# 03_cellular.net
KiCad netlist of a schematic drawn in Altium Designer
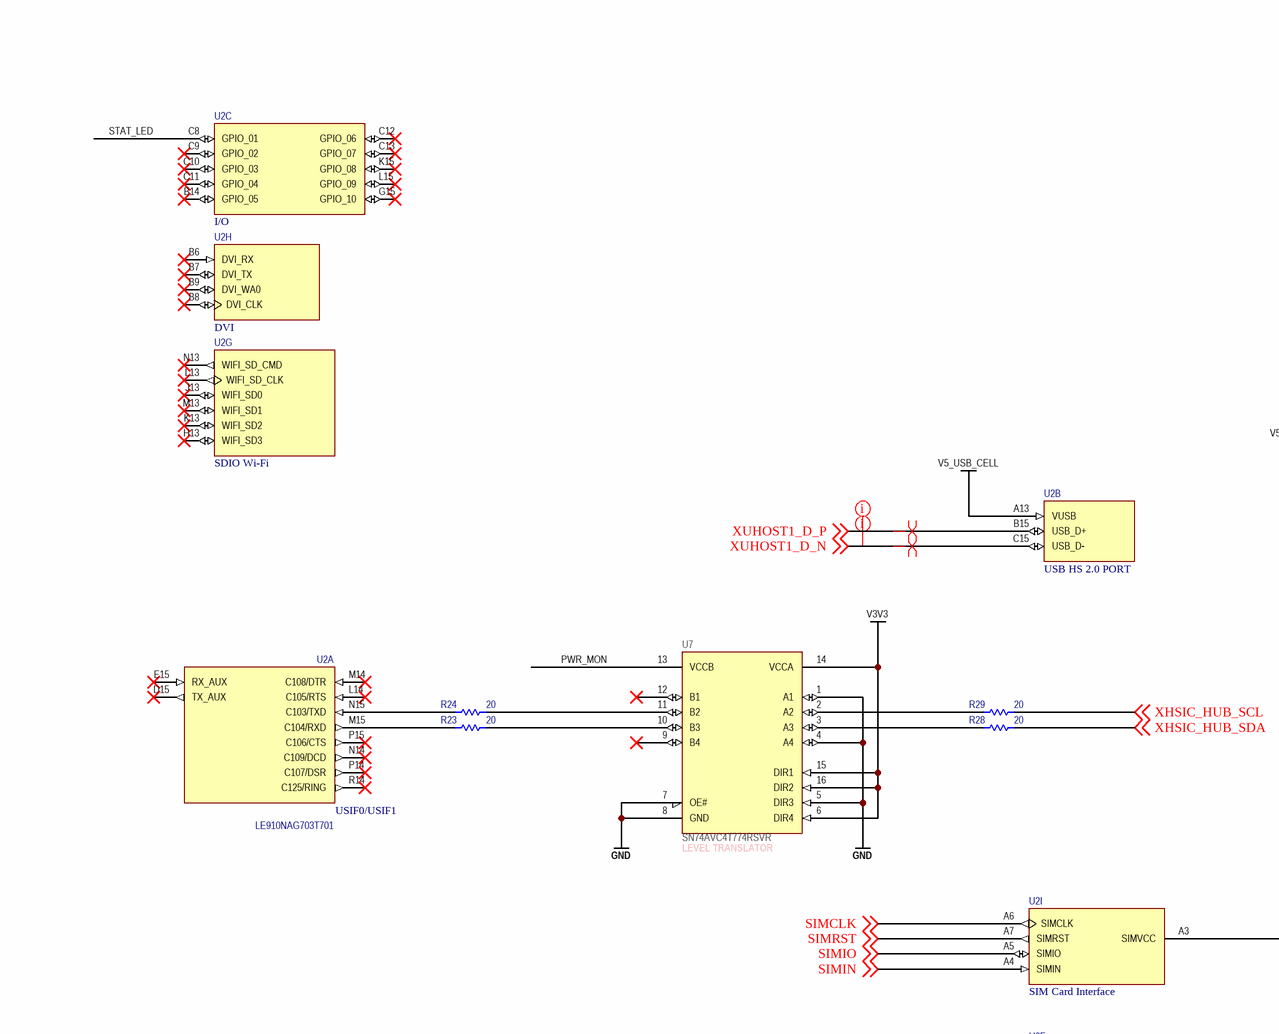
[diagram p0: 03_cellular.SchDoc, top left]
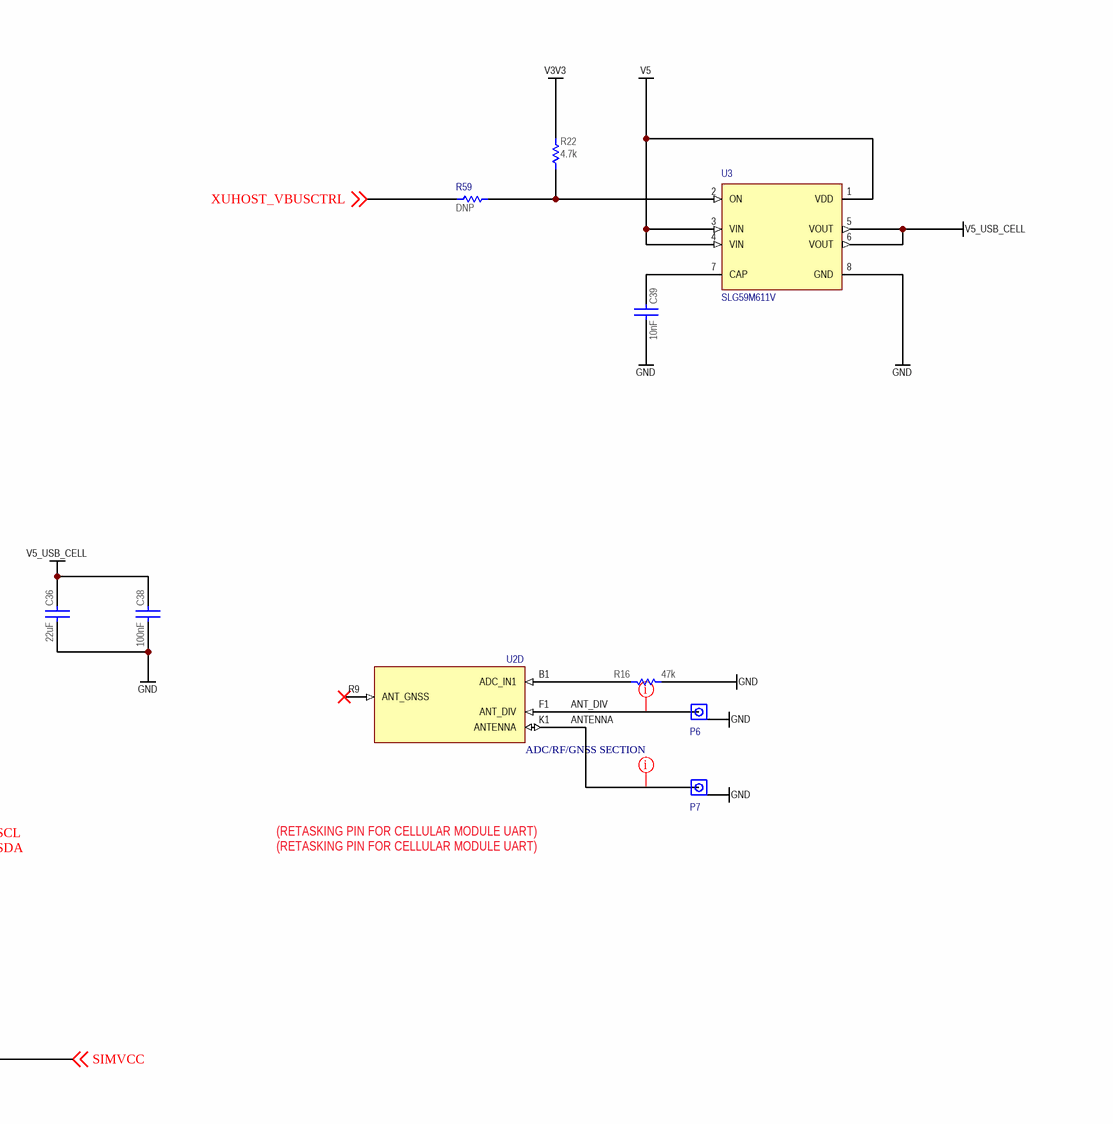
[diagram p1: 03_cellular.SchDoc, top right]
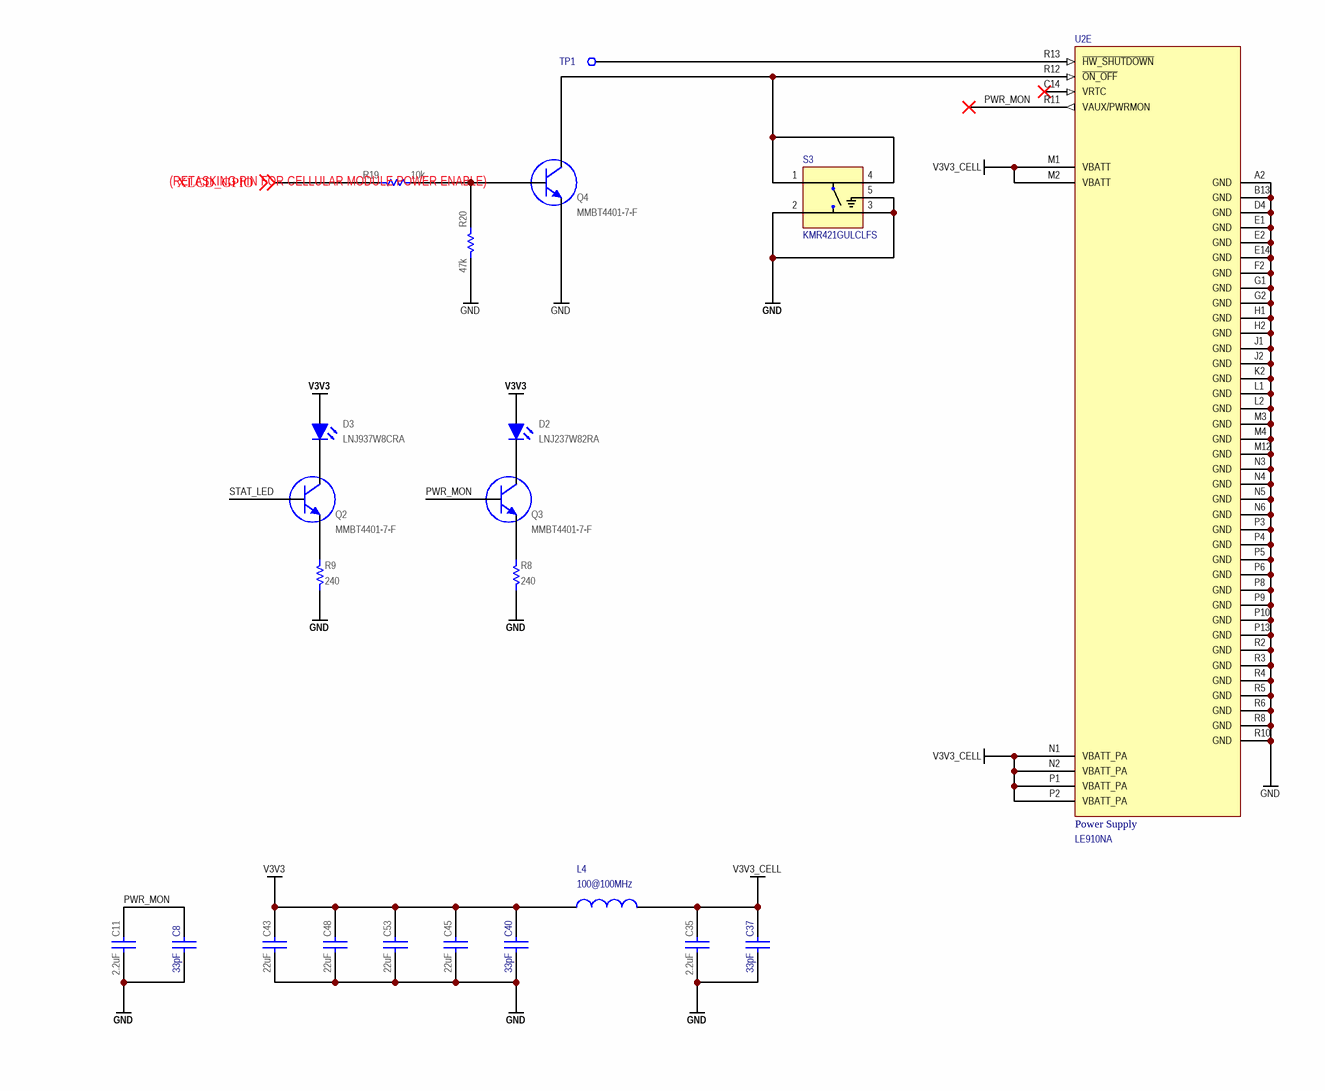
[diagram p2: 03_cellular.SchDoc, bottom left]
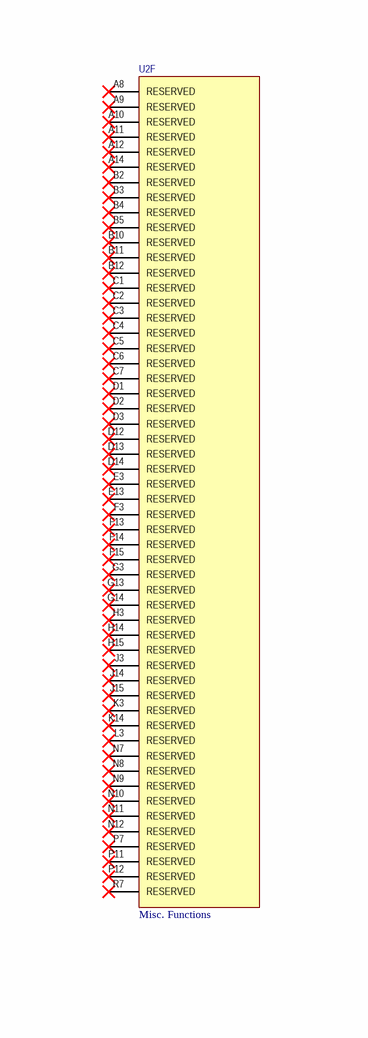
[diagram p3: 03_cellular.SchDoc, bottom right]

(export (version "E")
  (design (tool "Eeschema 10.0.6"))
  (components
    (comp (ref "C8")
      (value "33pF")
      (footprint "0402")
      (description "Ceramic Capacitor 33pF ±1% 50V NP0 0402")
      (fields (field (name "VOLTAGE") "50V") (field (name "MANUFACTURER") "Kemet"))
      (libsource (lib "Graviton") (part "CAP 0603"))
    )
    (comp (ref "C11")
      (value "2.2uF")
      (footprint "CAPC160X80X90L20N")
      (description "Ceramic Capacitor 2.2uF ±20% 10V X7R 0603")
      (fields (field (name "MANUFACTURER") "TDK") (field (name "TOLERANCE") "±20%"))
      (libsource (lib "generic") (part "CAP"))
    )
    (comp (ref "C35")
      (value "2.2uF")
      (footprint "CAPC160X80X90L20N")
      (description "Ceramic Capacitor 2.2uF ±20% 10V X7R 0603")
      (fields (field (name "MANUFACTURER") "TDK") (field (name "TOLERANCE") "±20%"))
      (libsource (lib "generic") (part "CAP"))
    )
    (comp (ref "C36")
      (value "22uF")
      (footprint "CAPC200X125X145L45N")
      (description "Ceramic Capacitor 22uF ±20% 10V X7S 0805")
      (fields (field (name "MANUFACTURER") "TDK") (field (name "TOLERANCE") "±20%"))
      (libsource (lib "generic") (part "CAP"))
    )
    (comp (ref "C37")
      (value "33pF")
      (footprint "0402")
      (description "Ceramic Capacitor 33pF ±1% 50V NP0 0402")
      (fields (field (name "VOLTAGE") "50V") (field (name "MANUFACTURER") "Kemet"))
      (libsource (lib "Graviton") (part "CAP 0603"))
    )
    (comp (ref "C38")
      (value "100nF")
      (footprint "CAPC100X50X55L25N")
      (description "Ceramic Capacitor 100nF ±10% 50V X7R 0402")
      (fields (field (name "MANUFACTURER") "Murata") (field (name "TOLERANCE") "±10%"))
      (libsource (lib "generic") (part "CAP"))
    )
    (comp (ref "C39")
      (value "10nF")
      (footprint "CAPC100X50X55L25N")
      (description "Ceramic Capacitor 10nF ±10% 50V X7R 0402")
      (fields (field (name "MANUFACTURER") "Murata") (field (name "TOLERANCE") "±10%"))
      (libsource (lib "generic") (part "CAP"))
    )
    (comp (ref "C40")
      (value "33pF")
      (footprint "0402")
      (description "Ceramic Capacitor 33pF ±1% 50V NP0 0402")
      (fields (field (name "VOLTAGE") "50V") (field (name "MANUFACTURER") "Kemet"))
      (libsource (lib "Graviton") (part "CAP 0603"))
    )
    (comp (ref "C43")
      (value "22uF")
      (footprint "CAPC200X125X145L45N")
      (description "Ceramic Capacitor 22uF ±20% 10V X7S 0805")
      (fields (field (name "MANUFACTURER") "TDK") (field (name "TOLERANCE") "±20%"))
      (libsource (lib "generic") (part "CAP"))
    )
    (comp (ref "C45")
      (value "22uF")
      (footprint "CAPC200X125X145L45N")
      (description "Ceramic Capacitor 22uF ±20% 10V X7S 0805")
      (fields (field (name "MANUFACTURER") "TDK") (field (name "TOLERANCE") "±20%"))
      (libsource (lib "generic") (part "CAP"))
    )
    (comp (ref "C48")
      (value "22uF")
      (footprint "CAPC200X125X145L45N")
      (description "Ceramic Capacitor 22uF ±20% 10V X7S 0805")
      (fields (field (name "MANUFACTURER") "TDK") (field (name "TOLERANCE") "±20%"))
      (libsource (lib "generic") (part "CAP"))
    )
    (comp (ref "C53")
      (value "22uF")
      (footprint "CAPC200X125X145L45N")
      (description "Ceramic Capacitor 22uF ±20% 10V X7S 0805")
      (fields (field (name "MANUFACTURER") "TDK") (field (name "TOLERANCE") "±20%"))
      (libsource (lib "generic") (part "CAP"))
    )
    (comp (ref "D2")
      (value "LNJ237W82RA")
      (footprint "0603_LED")
      (description "LED, SMT 0603, Color Red, 5mA, 1.85V")
      (fields (field (name "MANUFACTURER") "Panasonic"))
      (libsource (lib "generic") (part "LED0603RD"))
    )
    (comp (ref "D3")
      (value "LNJ937W8CRA")
      (footprint "0603_LED")
      (description "LED, SMT 0603, Color Blue, 5mA, 2.9V")
      (fields (field (name "MANUFACTURER") "Panasonic"))
      (libsource (lib "generic") (part "LED0603GR"))
    )
    (comp (ref "L4")
      (value "100@100MHz")
      (footprint "generic:0603")
      (description "Ferrite Bead 100-Ohm @ 100MHz 2A 0603")
      (fields (field (name "MANUFACTURER") "Murata") (field (name "TOLERANCE") "±25%"))
      (libsource (lib "altium-import") (part "root_0_IND 0402_"))
    )
    (comp (ref "P6")
      (value "U.FL-R-SMT(10)")
      (footprint "U.FL-R-SMT(10)")
      (description "Ultra Miniature Coaxial Jack, 50 Ohms")
      (fields (field (name "MANUFACTURER") "Hirose"))
      (libsource (lib "hirose") (part "U.FL-R-SMT(10)"))
    )
    (comp (ref "P7")
      (value "U.FL-R-SMT(10)")
      (footprint "U.FL-R-SMT(10)")
      (description "Ultra Miniature Coaxial Jack, 50 Ohms")
      (fields (field (name "MANUFACTURER") "Hirose"))
      (libsource (lib "hirose") (part "U.FL-R-SMT(10)"))
    )
    (comp (ref "Q2")
      (value "MMBT4401-7-F")
      (footprint "generic:SOT23")
      (description "NPN Small Signal Transistor SMD SOT-23")
      (fields (field (name "MANUFACTURER P/N") "MMBT4401-7-F") (field (name "MANUFACTURER") "Diodes, Inc."))
      (libsource (lib "diodes_inc") (part "MMBT4401-7-F"))
    )
    (comp (ref "Q3")
      (value "MMBT4401-7-F")
      (footprint "generic:SOT23")
      (description "NPN Small Signal Transistor SMD SOT-23")
      (fields (field (name "MANUFACTURER P/N") "MMBT4401-7-F") (field (name "MANUFACTURER") "Diodes, Inc."))
      (libsource (lib "diodes_inc") (part "MMBT4401-7-F"))
    )
    (comp (ref "Q4")
      (value "MMBT4401-7-F")
      (footprint "generic:SOT23")
      (description "NPN Small Signal Transistor SMD SOT-23")
      (fields (field (name "MANUFACTURER P/N") "MMBT4401-7-F") (field (name "MANUFACTURER") "Diodes, Inc."))
      (libsource (lib "diodes_inc") (part "MMBT4401-7-F"))
    )
    (comp (ref "R8")
      (value "240")
      (footprint "RESC1005X40N")
      (description "Thick Film Resistor 240 ±1% 0.1W 75V 0402")
      (fields (field (name "TOLERANCE") "±1%") (field (name "MANUFACTURER") "Panasonic"))
      (libsource (lib "generic") (part "RES"))
    )
    (comp (ref "R9")
      (value "240")
      (footprint "RESC1005X40N")
      (description "Thick Film Resistor 240 ±1% 0.1W 75V 0402")
      (fields (field (name "TOLERANCE") "±1%") (field (name "MANUFACTURER") "Panasonic"))
      (libsource (lib "generic") (part "RES"))
    )
    (comp (ref "R16")
      (value "47k")
      (footprint "RESC1005X40N")
      (description "Thick Film Resistor 47k ±1% 0.1W 75V 0402")
      (fields (field (name "TOLERANCE") "±1%") (field (name "MANUFACTURER") "Panasonic"))
      (libsource (lib "generic") (part "RES"))
    )
    (comp (ref "R19")
      (value "10k")
      (footprint "RESC1005X40N")
      (description "Thick Film Resistor 10k ±1% 0.1W 0402")
      (fields (field (name "TOLERANCE") "±1%") (field (name "MANUFACTURER") "Panasonic"))
      (libsource (lib "generic") (part "RES"))
    )
    (comp (ref "R20")
      (value "47k")
      (footprint "RESC1005X40N")
      (description "Thick Film Resistor 47k ±1% 0.1W 75V 0402")
      (fields (field (name "TOLERANCE") "±1%") (field (name "MANUFACTURER") "Panasonic"))
      (libsource (lib "generic") (part "RES"))
    )
    (comp (ref "R22")
      (value "4.7k")
      (footprint "RESC1005X40N")
      (description "Thick Film Resistor 4.7k ±1% 0.1W 75V 0402")
      (fields (field (name "TOLERANCE") "±1%") (field (name "MANUFACTURER") "Panasonic"))
      (libsource (lib "generic") (part "RES"))
    )
    (comp (ref "R23")
      (value "20")
      (footprint "generic:0402")
      (description "Thick Film Resistor 20 ±1% 0402")
      (fields (field (name "MANUFACTURER") "Panasonic") (field (name "TOLERANCE") "±1%"))
      (libsource (lib "altium-import") (part "root_2_RES 0402_"))
    )
    (comp (ref "R24")
      (value "20")
      (footprint "generic:0402")
      (description "Thick Film Resistor 20 ±1% 0402")
      (fields (field (name "MANUFACTURER") "Panasonic") (field (name "TOLERANCE") "±1%"))
      (libsource (lib "altium-import") (part "root_2_RES 0402_"))
    )
    (comp (ref "R28")
      (value "20")
      (footprint "generic:0402")
      (description "Thick Film Resistor 20 ±1% 0402")
      (fields (field (name "MANUFACTURER") "Panasonic") (field (name "TOLERANCE") "±1%"))
      (libsource (lib "altium-import") (part "root_2_RES 0402_"))
    )
    (comp (ref "R29")
      (value "20")
      (footprint "generic:0402")
      (description "Thick Film Resistor 20 ±1% 0402")
      (fields (field (name "MANUFACTURER") "Panasonic") (field (name "TOLERANCE") "±1%"))
      (libsource (lib "altium-import") (part "root_2_RES 0402_"))
    )
    (comp (ref "R59")
      (value "ERJ-2RKF20R0X")
      (footprint "generic:0402")
      (description "Thick Film Resistor 20 ±1% 0402")
      (fields
        (field (name "MANUFACTURER") "Panasonic")
        (field (name "TOLERANCE") "±1%")
        (field (name "DO NOT PLACE") "DNP")
      )
      (libsource (lib "altium-import") (part "root_2_RES 0402_"))
    )
    (comp (ref "S3")
      (value "KMR421GULCLFS")
      (footprint "SW_KMR421GULCLFS")
      (description "Switch Tactile N.O. SPST Round Button Gull Wing 0.05A 32VDC 1VA 200000Cycles 2N SMD Automotive T/R")
      (fields (field (name "MANUFACTURER") "C&K Components"))
      (libsource (lib "c&k") (part "KMR421GULCLFS"))
    )
    (comp (ref "TP1")
      (value "TEST_POINT_SMD_10")
      (footprint "generic:TEST_POINT_SMD_10")
      (description "Test Point SMD")
      (libsource (lib "generic") (part "TEST_POINT_SMD_10"))
    )
    (comp (ref "U2")
      (value "LE910NAG703T701")
      (footprint "LGA144S180P15X15_2820X2820X225_LE910NAG703T701(Primary)")
      (description "LE910 North America (AT&T, T-Mobile)")
      (fields (field (name "MANUFACTURER") "Telit") (field (name "MANUFACTURER P/N") "LE910NA"))
      (libsource (lib "") (part "LE910NAG703T701_1"))
    )
    (comp (ref "U3")
      (value "SLG59M611V")
      (footprint "DFN200X150X80-8N")
      (description "High-Side Load Switch")
      (fields (field (name "MANUFACTURER") "Silego"))
      (libsource (lib "silego") (part "SLG59M611V"))
    )
    (comp (ref "U7")
      (value "SN74AVC4T774RSVR")
      (footprint "RSV")
      (description "4-Bit Dual-Supply Bus Transceiver")
      (fields (field (name "MANUFACTURER") "Texas Instruments"))
      (libsource (lib "ti") (part "SN74AVC4T774RSVR"))
    )
  )
  (nets
    (net (code "1") (name "/ANTENNA") (class "Default")
      (node (ref "P7") (pin "1") (pinfunction "RF_1") (pintype "passive"))
      (node (ref "U2") (pin "K1") (pinfunction "ANTENNA_K1") (pintype "bidirectional"))
    )
    (net (code "2") (name "/ANT_DIV") (class "Default")
      (node (ref "P6") (pin "1") (pinfunction "RF_1") (pintype "passive"))
      (node (ref "U2") (pin "F1") (pinfunction "ANT_DIV_F1") (pintype "input"))
    )
    (net (code "3") (name "/PWR_MON") (class "Default")
      (node (ref "C11") (pin "2") (pinfunction "2_2") (pintype "passive"))
      (node (ref "C8") (pin "1") (pinfunction "1_1") (pintype "passive"))
      (node (ref "Q3") (pin "1") (pinfunction "B_1") (pintype "passive"))
      (node (ref "U2") (pin "R11") (pinfunction "VAUX/PWRMON_R11") (pintype "output"))
      (node (ref "U7") (pin "13") (pinfunction "VCCB_13") (pintype "power_in"))
    )
    (net (code "4") (name "/STAT_LED") (class "Default")
      (node (ref "Q2") (pin "1") (pinfunction "B_1") (pintype "passive"))
      (node (ref "U2") (pin "C8") (pinfunction "GPIO_01_C8") (pintype "bidirectional"))
    )
    (net (code "5") (name "GND") (class "Default")
      (node (ref "C11") (pin "1") (pinfunction "1_1") (pintype "passive"))
      (node (ref "C35") (pin "1") (pinfunction "1_1") (pintype "passive"))
      (node (ref "C36") (pin "1") (pinfunction "1_1") (pintype "passive"))
      (node (ref "C37") (pin "2") (pinfunction "2_2") (pintype "passive"))
      (node (ref "C38") (pin "1") (pinfunction "1_1") (pintype "passive"))
      (node (ref "C39") (pin "1") (pinfunction "1_1") (pintype "passive"))
      (node (ref "C40") (pin "2") (pinfunction "2_2") (pintype "passive"))
      (node (ref "C43") (pin "1") (pinfunction "1_1") (pintype "passive"))
      (node (ref "C45") (pin "1") (pinfunction "1_1") (pintype "passive"))
      (node (ref "C48") (pin "1") (pinfunction "1_1") (pintype "passive"))
      (node (ref "C53") (pin "1") (pinfunction "1_1") (pintype "passive"))
      (node (ref "C8") (pin "2") (pinfunction "2_2") (pintype "passive"))
      (node (ref "P6") (pin "2") (pinfunction "GND_2") (pintype "passive"))
      (node (ref "P7") (pin "2") (pinfunction "GND_2") (pintype "passive"))
      (node (ref "Q4") (pin "2") (pinfunction "E_2") (pintype "passive"))
      (node (ref "R16") (pin "1") (pinfunction "1_1") (pintype "passive"))
      (node (ref "R20") (pin "1") (pinfunction "1_1") (pintype "passive"))
      (node (ref "R8") (pin "2") (pinfunction "2_2") (pintype "passive"))
      (node (ref "R9") (pin "2") (pinfunction "2_2") (pintype "passive"))
      (node (ref "S3") (pin "2") (pinfunction "2_2") (pintype "passive"))
      (node (ref "S3") (pin "3") (pinfunction "3_3") (pintype "passive"))
      (node (ref "S3") (pin "5") (pinfunction "G_5") (pintype "power_in"))
      (node (ref "U2") (pin "A2") (pinfunction "GND_A2") (pintype "power_in"))
      (node (ref "U2") (pin "B13") (pinfunction "GND_B13") (pintype "power_in"))
      (node (ref "U2") (pin "D4") (pinfunction "GND_D4") (pintype "power_in"))
      (node (ref "U2") (pin "E1") (pinfunction "GND_E1") (pintype "power_in"))
      (node (ref "U2") (pin "E14") (pinfunction "GND_E14") (pintype "power_in"))
      (node (ref "U2") (pin "E2") (pinfunction "GND_E2") (pintype "power_in"))
      (node (ref "U2") (pin "F2") (pinfunction "GND_F2") (pintype "power_in"))
      (node (ref "U2") (pin "G1") (pinfunction "GND_G1") (pintype "power_in"))
      (node (ref "U2") (pin "G2") (pinfunction "GND_G2") (pintype "power_in"))
      (node (ref "U2") (pin "H1") (pinfunction "GND_H1") (pintype "power_in"))
      (node (ref "U2") (pin "H2") (pinfunction "GND_H2") (pintype "power_in"))
      (node (ref "U2") (pin "J1") (pinfunction "GND_J1") (pintype "power_in"))
      (node (ref "U2") (pin "J2") (pinfunction "GND_J2") (pintype "power_in"))
      (node (ref "U2") (pin "K2") (pinfunction "GND_K2") (pintype "power_in"))
      (node (ref "U2") (pin "L1") (pinfunction "GND_L1") (pintype "power_in"))
      (node (ref "U2") (pin "L2") (pinfunction "GND_L2") (pintype "power_in"))
      (node (ref "U2") (pin "M12") (pinfunction "GND_M12") (pintype "power_in"))
      (node (ref "U2") (pin "M3") (pinfunction "GND_M3") (pintype "power_in"))
      (node (ref "U2") (pin "M4") (pinfunction "GND_M4") (pintype "power_in"))
      (node (ref "U2") (pin "N3") (pinfunction "GND_N3") (pintype "power_in"))
      (node (ref "U2") (pin "N4") (pinfunction "GND_N4") (pintype "power_in"))
      (node (ref "U2") (pin "N5") (pinfunction "GND_N5") (pintype "power_in"))
      (node (ref "U2") (pin "N6") (pinfunction "GND_N6") (pintype "power_in"))
      (node (ref "U2") (pin "P10") (pinfunction "GND_P10") (pintype "power_in"))
      (node (ref "U2") (pin "P13") (pinfunction "GND_P13") (pintype "power_in"))
      (node (ref "U2") (pin "P3") (pinfunction "GND_P3") (pintype "power_in"))
      (node (ref "U2") (pin "P4") (pinfunction "GND_P4") (pintype "power_in"))
      (node (ref "U2") (pin "P5") (pinfunction "GND_P5") (pintype "power_in"))
      (node (ref "U2") (pin "P6") (pinfunction "GND_P6") (pintype "power_in"))
      (node (ref "U2") (pin "P8") (pinfunction "GND_P8") (pintype "power_in"))
      (node (ref "U2") (pin "P9") (pinfunction "GND_P9") (pintype "power_in"))
      (node (ref "U2") (pin "R10") (pinfunction "GND_R10") (pintype "power_in"))
      (node (ref "U2") (pin "R2") (pinfunction "GND_R2") (pintype "power_in"))
      (node (ref "U2") (pin "R3") (pinfunction "GND_R3") (pintype "power_in"))
      (node (ref "U2") (pin "R4") (pinfunction "GND_R4") (pintype "power_in"))
      (node (ref "U2") (pin "R5") (pinfunction "GND_R5") (pintype "power_in"))
      (node (ref "U2") (pin "R6") (pinfunction "GND_R6") (pintype "power_in"))
      (node (ref "U2") (pin "R8") (pinfunction "GND_R8") (pintype "power_in"))
      (node (ref "U3") (pin "8") (pinfunction "GND_8") (pintype "power_in"))
      (node (ref "U7") (pin "1") (pinfunction "A1_1") (pintype "bidirectional"))
      (node (ref "U7") (pin "4") (pinfunction "A4_4") (pintype "bidirectional"))
      (node (ref "U7") (pin "5") (pinfunction "DIR3_5") (pintype "input"))
      (node (ref "U7") (pin "7") (pinfunction "OE#_7") (pintype "passive"))
      (node (ref "U7") (pin "8") (pinfunction "GND_8") (pintype "power_in"))
    )
    (net (code "6") (name "Net-(D2-K)") (class "Default")
      (node (ref "D2") (pin "2") (pinfunction "K_2") (pintype "passive"))
      (node (ref "Q3") (pin "3") (pinfunction "C_3") (pintype "passive"))
    )
    (net (code "7") (name "Net-(D3-K)") (class "Default")
      (node (ref "D3") (pin "2") (pinfunction "K_2") (pintype "passive"))
      (node (ref "Q2") (pin "3") (pinfunction "C_3") (pintype "passive"))
    )
    (net (code "8") (name "Net-(Q2-E)") (class "Default")
      (node (ref "Q2") (pin "2") (pinfunction "E_2") (pintype "passive"))
      (node (ref "R9") (pin "1") (pinfunction "1_1") (pintype "passive"))
    )
    (net (code "9") (name "Net-(Q3-E)") (class "Default")
      (node (ref "Q3") (pin "2") (pinfunction "E_2") (pintype "passive"))
      (node (ref "R8") (pin "1") (pinfunction "1_1") (pintype "passive"))
    )
    (net (code "10") (name "Net-(Q4-B)") (class "Default")
      (node (ref "Q4") (pin "1") (pinfunction "B_1") (pintype "passive"))
      (node (ref "R19") (pin "1") (pinfunction "1_1") (pintype "passive"))
      (node (ref "R20") (pin "2") (pinfunction "2_2") (pintype "passive"))
    )
    (net (code "11") (name "Net-(Q4-C)") (class "Default")
      (node (ref "Q4") (pin "3") (pinfunction "C_3") (pintype "passive"))
      (node (ref "S3") (pin "1") (pinfunction "1_1") (pintype "passive"))
      (node (ref "S3") (pin "4") (pinfunction "4_4") (pintype "passive"))
      (node (ref "U2") (pin "R12") (pinfunction "~{ON_OFF}_R12") (pintype "input"))
    )
    (net (code "12") (name "Net-(U2A-C103{slash}TXD)") (class "Default")
      (node (ref "R24") (pin "2") (pinfunction "2_2") (pintype "passive"))
      (node (ref "U2") (pin "N15") (pinfunction "C103/TXD_N15") (pintype "input"))
    )
    (net (code "13") (name "Net-(U2A-C104{slash}RXD)") (class "Default")
      (node (ref "R23") (pin "2") (pinfunction "2_2") (pintype "passive"))
      (node (ref "U2") (pin "M15") (pinfunction "C104/RXD_M15") (pintype "output"))
    )
    (net (code "14") (name "Net-(U2D-ADC_IN1)") (class "Default")
      (node (ref "R16") (pin "2") (pinfunction "2_2") (pintype "passive"))
      (node (ref "U2") (pin "B1") (pinfunction "ADC_IN1_B1") (pintype "input"))
    )
    (net (code "15") (name "Net-(U2E-~{HW_SHUTDOWN})") (class "Default")
      (node (ref "TP1") (pin "1") (pinfunction "1_1") (pintype "passive"))
      (node (ref "U2") (pin "R13") (pinfunction "~{HW_SHUTDOWN}_R13") (pintype "input"))
    )
    (net (code "16") (name "Net-(U3-CAP)") (class "Default")
      (node (ref "C39") (pin "2") (pinfunction "2_2") (pintype "passive"))
      (node (ref "U3") (pin "7") (pinfunction "CAP_7") (pintype "passive"))
    )
    (net (code "17") (name "Net-(U3-ON)") (class "Default")
      (node (ref "R22") (pin "1") (pinfunction "1_1") (pintype "passive"))
      (node (ref "R59") (pin "1") (pinfunction "1_1") (pintype "passive"))
      (node (ref "U3") (pin "2") (pinfunction "ON_2") (pintype "input"))
    )
    (net (code "18") (name "Net-(U7-A2)") (class "Default")
      (node (ref "R29") (pin "2") (pinfunction "2_2") (pintype "passive"))
      (node (ref "U7") (pin "2") (pinfunction "A2_2") (pintype "bidirectional"))
    )
    (net (code "19") (name "Net-(U7-A3)") (class "Default")
      (node (ref "R28") (pin "2") (pinfunction "2_2") (pintype "passive"))
      (node (ref "U7") (pin "3") (pinfunction "A3_3") (pintype "bidirectional"))
    )
    (net (code "20") (name "Net-(U7-B2)") (class "Default")
      (node (ref "R24") (pin "1") (pinfunction "1_1") (pintype "passive"))
      (node (ref "U7") (pin "11") (pinfunction "B2_11") (pintype "bidirectional"))
    )
    (net (code "21") (name "Net-(U7-B3)") (class "Default")
      (node (ref "R23") (pin "1") (pinfunction "1_1") (pintype "passive"))
      (node (ref "U7") (pin "10") (pinfunction "B3_10") (pintype "bidirectional"))
    )
    (net (code "22") (name "SIMCLK") (class "Default")
      (node (ref "U2") (pin "A6") (pinfunction "SIMCLK_A6") (pintype "output"))
    )
    (net (code "23") (name "SIMIN") (class "Default")
      (node (ref "U2") (pin "A4") (pinfunction "SIMIN_A4") (pintype "input"))
    )
    (net (code "24") (name "SIMIO") (class "Default")
      (node (ref "U2") (pin "A5") (pinfunction "SIMIO_A5") (pintype "bidirectional"))
    )
    (net (code "25") (name "SIMRST") (class "Default")
      (node (ref "U2") (pin "A7") (pinfunction "SIMRST_A7") (pintype "output"))
    )
    (net (code "26") (name "SIMVCC") (class "Default")
      (node (ref "U2") (pin "A3") (pinfunction "SIMVCC_A3") (pintype "power_in"))
    )
    (net (code "27") (name "V3V3") (class "Default")
      (node (ref "C40") (pin "1") (pinfunction "1_1") (pintype "passive"))
      (node (ref "C43") (pin "2") (pinfunction "2_2") (pintype "passive"))
      (node (ref "C45") (pin "2") (pinfunction "2_2") (pintype "passive"))
      (node (ref "C48") (pin "2") (pinfunction "2_2") (pintype "passive"))
      (node (ref "C53") (pin "2") (pinfunction "2_2") (pintype "passive"))
      (node (ref "D2") (pin "1") (pinfunction "A_1") (pintype "passive"))
      (node (ref "D3") (pin "1") (pinfunction "A_1") (pintype "passive"))
      (node (ref "L4") (pin "1") (pinfunction "1_1") (pintype "passive"))
      (node (ref "R22") (pin "2") (pinfunction "2_2") (pintype "passive"))
      (node (ref "U7") (pin "14") (pinfunction "VCCA_14") (pintype "power_in"))
      (node (ref "U7") (pin "15") (pinfunction "DIR1_15") (pintype "input"))
      (node (ref "U7") (pin "16") (pinfunction "DIR2_16") (pintype "input"))
      (node (ref "U7") (pin "6") (pinfunction "DIR4_6") (pintype "input"))
    )
    (net (code "28") (name "V3V3_CELL") (class "Default")
      (node (ref "C35") (pin "2") (pinfunction "2_2") (pintype "passive"))
      (node (ref "C37") (pin "1") (pinfunction "1_1") (pintype "passive"))
      (node (ref "L4") (pin "2") (pinfunction "2_2") (pintype "passive"))
      (node (ref "U2") (pin "M1") (pinfunction "VBATT_M1") (pintype "power_in"))
      (node (ref "U2") (pin "M2") (pinfunction "VBATT_M2") (pintype "power_in"))
      (node (ref "U2") (pin "N1") (pinfunction "VBATT_PA_N1") (pintype "power_in"))
      (node (ref "U2") (pin "N2") (pinfunction "VBATT_PA_N2") (pintype "power_in"))
      (node (ref "U2") (pin "P1") (pinfunction "VBATT_PA_P1") (pintype "power_in"))
      (node (ref "U2") (pin "P2") (pinfunction "VBATT_PA_P2") (pintype "power_in"))
    )
    (net (code "29") (name "V5") (class "Default")
      (node (ref "U3") (pin "1") (pinfunction "VDD_1") (pintype "power_in"))
      (node (ref "U3") (pin "3") (pinfunction "VIN_3") (pintype "input"))
      (node (ref "U3") (pin "4") (pinfunction "VIN_4") (pintype "input"))
    )
    (net (code "30") (name "V5_USB_CELL") (class "Default")
      (node (ref "C36") (pin "2") (pinfunction "2_2") (pintype "passive"))
      (node (ref "C38") (pin "2") (pinfunction "2_2") (pintype "passive"))
      (node (ref "U2") (pin "A13") (pinfunction "VUSB_A13") (pintype "input"))
      (node (ref "U3") (pin "5") (pinfunction "VOUT_5") (pintype "output"))
      (node (ref "U3") (pin "6") (pinfunction "VOUT_6") (pintype "output"))
    )
    (net (code "31") (name "XHSIC_HUB_SCL") (class "Default")
      (node (ref "R29") (pin "1") (pinfunction "1_1") (pintype "passive"))
    )
    (net (code "32") (name "XHSIC_HUB_SDA") (class "Default")
      (node (ref "R28") (pin "1") (pinfunction "1_1") (pintype "passive"))
    )
    (net (code "33") (name "XLCD_GPIO") (class "Default")
      (node (ref "R19") (pin "2") (pinfunction "2_2") (pintype "passive"))
    )
    (net (code "34") (name "XUHOST1_D_N") (class "Default")
      (node (ref "U2") (pin "C15") (pinfunction "USB_D-_C15") (pintype "bidirectional"))
    )
    (net (code "35") (name "XUHOST1_D_P") (class "Default")
      (node (ref "U2") (pin "B15") (pinfunction "USB_D+_B15") (pintype "bidirectional"))
    )
    (net (code "36") (name "XUHOST_VBUSCTRL") (class "Default")
      (node (ref "R59") (pin "2") (pinfunction "2_2") (pintype "passive"))
    )
    (net (code "37") (name "unconnected-(U2A-C105{slash}RTS-PadL14)") (class "Default")
      (node (ref "U2") (pin "L14") (pinfunction "C105/RTS_L14") (pintype "input+no_connect"))
    )
    (net (code "38") (name "unconnected-(U2A-C106{slash}CTS-PadP15)") (class "Default")
      (node (ref "U2") (pin "P15") (pinfunction "C106/CTS_P15") (pintype "output+no_connect"))
    )
    (net (code "39") (name "unconnected-(U2A-C107{slash}DSR-PadP14)") (class "Default")
      (node (ref "U2") (pin "P14") (pinfunction "C107/DSR_P14") (pintype "output+no_connect"))
    )
    (net (code "40") (name "unconnected-(U2A-C108{slash}DTR-PadM14)") (class "Default")
      (node (ref "U2") (pin "M14") (pinfunction "C108/DTR_M14") (pintype "input+no_connect"))
    )
    (net (code "41") (name "unconnected-(U2A-C109{slash}DCD-PadN14)") (class "Default")
      (node (ref "U2") (pin "N14") (pinfunction "C109/DCD_N14") (pintype "output+no_connect"))
    )
    (net (code "42") (name "unconnected-(U2A-C125{slash}RING-PadR14)") (class "Default")
      (node (ref "U2") (pin "R14") (pinfunction "C125/RING_R14") (pintype "output+no_connect"))
    )
    (net (code "43") (name "unconnected-(U2A-RX_AUX-PadE15)") (class "Default")
      (node (ref "U2") (pin "E15") (pinfunction "RX_AUX_E15") (pintype "input+no_connect"))
    )
    (net (code "44") (name "unconnected-(U2A-TX_AUX-PadD15)") (class "Default")
      (node (ref "U2") (pin "D15") (pinfunction "TX_AUX_D15") (pintype "output+no_connect"))
    )
    (net (code "45") (name "unconnected-(U2C-GPIO_02-PadC9)") (class "Default")
      (node (ref "U2") (pin "C9") (pinfunction "GPIO_02_C9") (pintype "bidirectional+no_connect"))
    )
    (net (code "46") (name "unconnected-(U2C-GPIO_03-PadC10)") (class "Default")
      (node (ref "U2") (pin "C10") (pinfunction "GPIO_03_C10") (pintype "bidirectional+no_connect"))
    )
    (net (code "47") (name "unconnected-(U2C-GPIO_04-PadC11)") (class "Default")
      (node (ref "U2") (pin "C11") (pinfunction "GPIO_04_C11") (pintype "bidirectional+no_connect"))
    )
    (net (code "48") (name "unconnected-(U2C-GPIO_05-PadB14)") (class "Default")
      (node (ref "U2") (pin "B14") (pinfunction "GPIO_05_B14") (pintype "bidirectional+no_connect"))
    )
    (net (code "49") (name "unconnected-(U2C-GPIO_06-PadC12)") (class "Default")
      (node (ref "U2") (pin "C12") (pinfunction "GPIO_06_C12") (pintype "bidirectional+no_connect"))
    )
    (net (code "50") (name "unconnected-(U2C-GPIO_07-PadC13)") (class "Default")
      (node (ref "U2") (pin "C13") (pinfunction "GPIO_07_C13") (pintype "bidirectional+no_connect"))
    )
    (net (code "51") (name "unconnected-(U2C-GPIO_08-PadK15)") (class "Default")
      (node (ref "U2") (pin "K15") (pinfunction "GPIO_08_K15") (pintype "bidirectional+no_connect"))
    )
    (net (code "52") (name "unconnected-(U2C-GPIO_09-PadL15)") (class "Default")
      (node (ref "U2") (pin "L15") (pinfunction "GPIO_09_L15") (pintype "bidirectional+no_connect"))
    )
    (net (code "53") (name "unconnected-(U2C-GPIO_10-PadG15)") (class "Default")
      (node (ref "U2") (pin "G15") (pinfunction "GPIO_10_G15") (pintype "bidirectional+no_connect"))
    )
    (net (code "54") (name "unconnected-(U2D-ANT_GNSS-PadR9)") (class "Default")
      (node (ref "U2") (pin "R9") (pinfunction "ANT_GNSS_R9") (pintype "input+no_connect"))
    )
    (net (code "55") (name "unconnected-(U2E-VRTC-PadC14)") (class "Default")
      (node (ref "U2") (pin "C14") (pinfunction "VRTC_C14") (pintype "input+no_connect"))
    )
    (net (code "56") (name "unconnected-(U2F-RESERVED-PadA8)") (class "Default")
      (node (ref "U2") (pin "A8") (pinfunction "RESERVED_A8") (pintype "passive+no_connect"))
    )
    (net (code "57") (name "unconnected-(U2F-RESERVED-PadA9)") (class "Default")
      (node (ref "U2") (pin "A9") (pinfunction "RESERVED_A9") (pintype "passive+no_connect"))
    )
    (net (code "58") (name "unconnected-(U2F-RESERVED-PadA10)") (class "Default")
      (node (ref "U2") (pin "A10") (pinfunction "RESERVED_A10") (pintype "passive+no_connect"))
    )
    (net (code "59") (name "unconnected-(U2F-RESERVED-PadA11)") (class "Default")
      (node (ref "U2") (pin "A11") (pinfunction "RESERVED_A11") (pintype "passive+no_connect"))
    )
    (net (code "60") (name "unconnected-(U2F-RESERVED-PadA12)") (class "Default")
      (node (ref "U2") (pin "A12") (pinfunction "RESERVED_A12") (pintype "passive+no_connect"))
    )
    (net (code "61") (name "unconnected-(U2F-RESERVED-PadA14)") (class "Default")
      (node (ref "U2") (pin "A14") (pinfunction "RESERVED_A14") (pintype "passive+no_connect"))
    )
    (net (code "62") (name "unconnected-(U2F-RESERVED-PadB2)") (class "Default")
      (node (ref "U2") (pin "B2") (pinfunction "RESERVED_B2") (pintype "passive+no_connect"))
    )
    (net (code "63") (name "unconnected-(U2F-RESERVED-PadB3)") (class "Default")
      (node (ref "U2") (pin "B3") (pinfunction "RESERVED_B3") (pintype "passive+no_connect"))
    )
    (net (code "64") (name "unconnected-(U2F-RESERVED-PadB4)") (class "Default")
      (node (ref "U2") (pin "B4") (pinfunction "RESERVED_B4") (pintype "passive+no_connect"))
    )
    (net (code "65") (name "unconnected-(U2F-RESERVED-PadB5)") (class "Default")
      (node (ref "U2") (pin "B5") (pinfunction "RESERVED_B5") (pintype "passive+no_connect"))
    )
    (net (code "66") (name "unconnected-(U2F-RESERVED-PadB10)") (class "Default")
      (node (ref "U2") (pin "B10") (pinfunction "RESERVED_B10") (pintype "passive+no_connect"))
    )
    (net (code "67") (name "unconnected-(U2F-RESERVED-PadB11)") (class "Default")
      (node (ref "U2") (pin "B11") (pinfunction "RESERVED_B11") (pintype "passive+no_connect"))
    )
    (net (code "68") (name "unconnected-(U2F-RESERVED-PadB12)") (class "Default")
      (node (ref "U2") (pin "B12") (pinfunction "RESERVED_B12") (pintype "passive+no_connect"))
    )
    (net (code "69") (name "unconnected-(U2F-RESERVED-PadC1)") (class "Default")
      (node (ref "U2") (pin "C1") (pinfunction "RESERVED_C1") (pintype "passive+no_connect"))
    )
    (net (code "70") (name "unconnected-(U2F-RESERVED-PadC2)") (class "Default")
      (node (ref "U2") (pin "C2") (pinfunction "RESERVED_C2") (pintype "passive+no_connect"))
    )
    (net (code "71") (name "unconnected-(U2F-RESERVED-PadC3)") (class "Default")
      (node (ref "U2") (pin "C3") (pinfunction "RESERVED_C3") (pintype "passive+no_connect"))
    )
    (net (code "72") (name "unconnected-(U2F-RESERVED-PadC4)") (class "Default")
      (node (ref "U2") (pin "C4") (pinfunction "RESERVED_C4") (pintype "passive+no_connect"))
    )
    (net (code "73") (name "unconnected-(U2F-RESERVED-PadC5)") (class "Default")
      (node (ref "U2") (pin "C5") (pinfunction "RESERVED_C5") (pintype "passive+no_connect"))
    )
    (net (code "74") (name "unconnected-(U2F-RESERVED-PadC6)") (class "Default")
      (node (ref "U2") (pin "C6") (pinfunction "RESERVED_C6") (pintype "passive+no_connect"))
    )
    (net (code "75") (name "unconnected-(U2F-RESERVED-PadC7)") (class "Default")
      (node (ref "U2") (pin "C7") (pinfunction "RESERVED_C7") (pintype "passive+no_connect"))
    )
    (net (code "76") (name "unconnected-(U2F-RESERVED-PadD1)") (class "Default")
      (node (ref "U2") (pin "D1") (pinfunction "RESERVED_D1") (pintype "passive+no_connect"))
    )
    (net (code "77") (name "unconnected-(U2F-RESERVED-PadD2)") (class "Default")
      (node (ref "U2") (pin "D2") (pinfunction "RESERVED_D2") (pintype "passive+no_connect"))
    )
    (net (code "78") (name "unconnected-(U2F-RESERVED-PadD3)") (class "Default")
      (node (ref "U2") (pin "D3") (pinfunction "RESERVED_D3") (pintype "passive+no_connect"))
    )
    (net (code "79") (name "unconnected-(U2F-RESERVED-PadD12)") (class "Default")
      (node (ref "U2") (pin "D12") (pinfunction "RESERVED_D12") (pintype "passive+no_connect"))
    )
    (net (code "80") (name "unconnected-(U2F-RESERVED-PadD13)") (class "Default")
      (node (ref "U2") (pin "D13") (pinfunction "RESERVED_D13") (pintype "passive+no_connect"))
    )
    (net (code "81") (name "unconnected-(U2F-RESERVED-PadD14)") (class "Default")
      (node (ref "U2") (pin "D14") (pinfunction "RESERVED_D14") (pintype "passive+no_connect"))
    )
    (net (code "82") (name "unconnected-(U2F-RESERVED-PadE3)") (class "Default")
      (node (ref "U2") (pin "E3") (pinfunction "RESERVED_E3") (pintype "passive+no_connect"))
    )
    (net (code "83") (name "unconnected-(U2F-RESERVED-PadE13)") (class "Default")
      (node (ref "U2") (pin "E13") (pinfunction "RESERVED_E13") (pintype "passive+no_connect"))
    )
    (net (code "84") (name "unconnected-(U2F-RESERVED-PadF3)") (class "Default")
      (node (ref "U2") (pin "F3") (pinfunction "RESERVED_F3") (pintype "passive+no_connect"))
    )
    (net (code "85") (name "unconnected-(U2F-RESERVED-PadF13)") (class "Default")
      (node (ref "U2") (pin "F13") (pinfunction "RESERVED_F13") (pintype "passive+no_connect"))
    )
    (net (code "86") (name "unconnected-(U2F-RESERVED-PadF14)") (class "Default")
      (node (ref "U2") (pin "F14") (pinfunction "RESERVED_F14") (pintype "passive+no_connect"))
    )
    (net (code "87") (name "unconnected-(U2F-RESERVED-PadF15)") (class "Default")
      (node (ref "U2") (pin "F15") (pinfunction "RESERVED_F15") (pintype "passive+no_connect"))
    )
    (net (code "88") (name "unconnected-(U2F-RESERVED-PadG3)") (class "Default")
      (node (ref "U2") (pin "G3") (pinfunction "RESERVED_G3") (pintype "passive+no_connect"))
    )
    (net (code "89") (name "unconnected-(U2F-RESERVED-PadG13)") (class "Default")
      (node (ref "U2") (pin "G13") (pinfunction "RESERVED_G13") (pintype "passive+no_connect"))
    )
    (net (code "90") (name "unconnected-(U2F-RESERVED-PadG14)") (class "Default")
      (node (ref "U2") (pin "G14") (pinfunction "RESERVED_G14") (pintype "passive+no_connect"))
    )
    (net (code "91") (name "unconnected-(U2F-RESERVED-PadH3)") (class "Default")
      (node (ref "U2") (pin "H3") (pinfunction "RESERVED_H3") (pintype "passive+no_connect"))
    )
    (net (code "92") (name "unconnected-(U2F-RESERVED-PadH14)") (class "Default")
      (node (ref "U2") (pin "H14") (pinfunction "RESERVED_H14") (pintype "passive+no_connect"))
    )
    (net (code "93") (name "unconnected-(U2F-RESERVED-PadH15)") (class "Default")
      (node (ref "U2") (pin "H15") (pinfunction "RESERVED_H15") (pintype "passive+no_connect"))
    )
    (net (code "94") (name "unconnected-(U2F-RESERVED-PadJ3)") (class "Default")
      (node (ref "U2") (pin "J3") (pinfunction "RESERVED_J3") (pintype "passive+no_connect"))
    )
    (net (code "95") (name "unconnected-(U2F-RESERVED-PadJ14)") (class "Default")
      (node (ref "U2") (pin "J14") (pinfunction "RESERVED_J14") (pintype "passive+no_connect"))
    )
    (net (code "96") (name "unconnected-(U2F-RESERVED-PadJ15)") (class "Default")
      (node (ref "U2") (pin "J15") (pinfunction "RESERVED_J15") (pintype "passive+no_connect"))
    )
    (net (code "97") (name "unconnected-(U2F-RESERVED-PadK3)") (class "Default")
      (node (ref "U2") (pin "K3") (pinfunction "RESERVED_K3") (pintype "passive+no_connect"))
    )
    (net (code "98") (name "unconnected-(U2F-RESERVED-PadK14)") (class "Default")
      (node (ref "U2") (pin "K14") (pinfunction "RESERVED_K14") (pintype "passive+no_connect"))
    )
    (net (code "99") (name "unconnected-(U2F-RESERVED-PadL3)") (class "Default")
      (node (ref "U2") (pin "L3") (pinfunction "RESERVED_L3") (pintype "passive+no_connect"))
    )
    (net (code "100") (name "unconnected-(U2F-RESERVED-PadN7)") (class "Default")
      (node (ref "U2") (pin "N7") (pinfunction "RESERVED_N7") (pintype "passive+no_connect"))
    )
    (net (code "101") (name "unconnected-(U2F-RESERVED-PadN8)") (class "Default")
      (node (ref "U2") (pin "N8") (pinfunction "RESERVED_N8") (pintype "passive+no_connect"))
    )
    (net (code "102") (name "unconnected-(U2F-RESERVED-PadN9)") (class "Default")
      (node (ref "U2") (pin "N9") (pinfunction "RESERVED_N9") (pintype "passive+no_connect"))
    )
    (net (code "103") (name "unconnected-(U2F-RESERVED-PadN10)") (class "Default")
      (node (ref "U2") (pin "N10") (pinfunction "RESERVED_N10") (pintype "passive+no_connect"))
    )
    (net (code "104") (name "unconnected-(U2F-RESERVED-PadN11)") (class "Default")
      (node (ref "U2") (pin "N11") (pinfunction "RESERVED_N11") (pintype "passive+no_connect"))
    )
    (net (code "105") (name "unconnected-(U2F-RESERVED-PadN12)") (class "Default")
      (node (ref "U2") (pin "N12") (pinfunction "RESERVED_N12") (pintype "passive+no_connect"))
    )
    (net (code "106") (name "unconnected-(U2F-RESERVED-PadP7)") (class "Default")
      (node (ref "U2") (pin "P7") (pinfunction "RESERVED_P7") (pintype "passive+no_connect"))
    )
    (net (code "107") (name "unconnected-(U2F-RESERVED-PadP11)") (class "Default")
      (node (ref "U2") (pin "P11") (pinfunction "RESERVED_P11") (pintype "passive+no_connect"))
    )
    (net (code "108") (name "unconnected-(U2F-RESERVED-PadP12)") (class "Default")
      (node (ref "U2") (pin "P12") (pinfunction "RESERVED_P12") (pintype "passive+no_connect"))
    )
    (net (code "109") (name "unconnected-(U2F-RESERVED-PadR7)") (class "Default")
      (node (ref "U2") (pin "R7") (pinfunction "RESERVED_R7") (pintype "passive+no_connect"))
    )
    (net (code "110") (name "unconnected-(U2G-WIFI_SD0-PadJ13)") (class "Default")
      (node (ref "U2") (pin "J13") (pinfunction "WIFI_SD0_J13") (pintype "bidirectional+no_connect"))
    )
    (net (code "111") (name "unconnected-(U2G-WIFI_SD1-PadM13)") (class "Default")
      (node (ref "U2") (pin "M13") (pinfunction "WIFI_SD1_M13") (pintype "bidirectional+no_connect"))
    )
    (net (code "112") (name "unconnected-(U2G-WIFI_SD2-PadK13)") (class "Default")
      (node (ref "U2") (pin "K13") (pinfunction "WIFI_SD2_K13") (pintype "bidirectional+no_connect"))
    )
    (net (code "113") (name "unconnected-(U2G-WIFI_SD3-PadH13)") (class "Default")
      (node (ref "U2") (pin "H13") (pinfunction "WIFI_SD3_H13") (pintype "bidirectional+no_connect"))
    )
    (net (code "114") (name "unconnected-(U2G-WIFI_SD_CLK-PadL13)") (class "Default")
      (node (ref "U2") (pin "L13") (pinfunction "WIFI_SD_CLK_L13") (pintype "output+no_connect"))
    )
    (net (code "115") (name "unconnected-(U2G-WIFI_SD_CMD-PadN13)") (class "Default")
      (node (ref "U2") (pin "N13") (pinfunction "WIFI_SD_CMD_N13") (pintype "output+no_connect"))
    )
    (net (code "116") (name "unconnected-(U2H-DVI_CLK-PadB8)") (class "Default")
      (node (ref "U2") (pin "B8") (pinfunction "DVI_CLK_B8") (pintype "bidirectional+no_connect"))
    )
    (net (code "117") (name "unconnected-(U2H-DVI_RX-PadB6)") (class "Default")
      (node (ref "U2") (pin "B6") (pinfunction "DVI_RX_B6") (pintype "input+no_connect"))
    )
    (net (code "118") (name "unconnected-(U2H-DVI_TX-PadB7)") (class "Default")
      (node (ref "U2") (pin "B7") (pinfunction "DVI_TX_B7") (pintype "bidirectional+no_connect"))
    )
    (net (code "119") (name "unconnected-(U2H-DVI_WA0-PadB9)") (class "Default")
      (node (ref "U2") (pin "B9") (pinfunction "DVI_WA0_B9") (pintype "bidirectional+no_connect"))
    )
    (net (code "120") (name "unconnected-(U7-B1-Pad12)") (class "Default")
      (node (ref "U7") (pin "12") (pinfunction "B1_12") (pintype "bidirectional+no_connect"))
    )
    (net (code "121") (name "unconnected-(U7-B4-Pad9)") (class "Default")
      (node (ref "U7") (pin "9") (pinfunction "B4_9") (pintype "bidirectional+no_connect"))
    )
  )
)
